# inktime_schematic.net
KiCad netlist of a schematic drawn in EAGLE
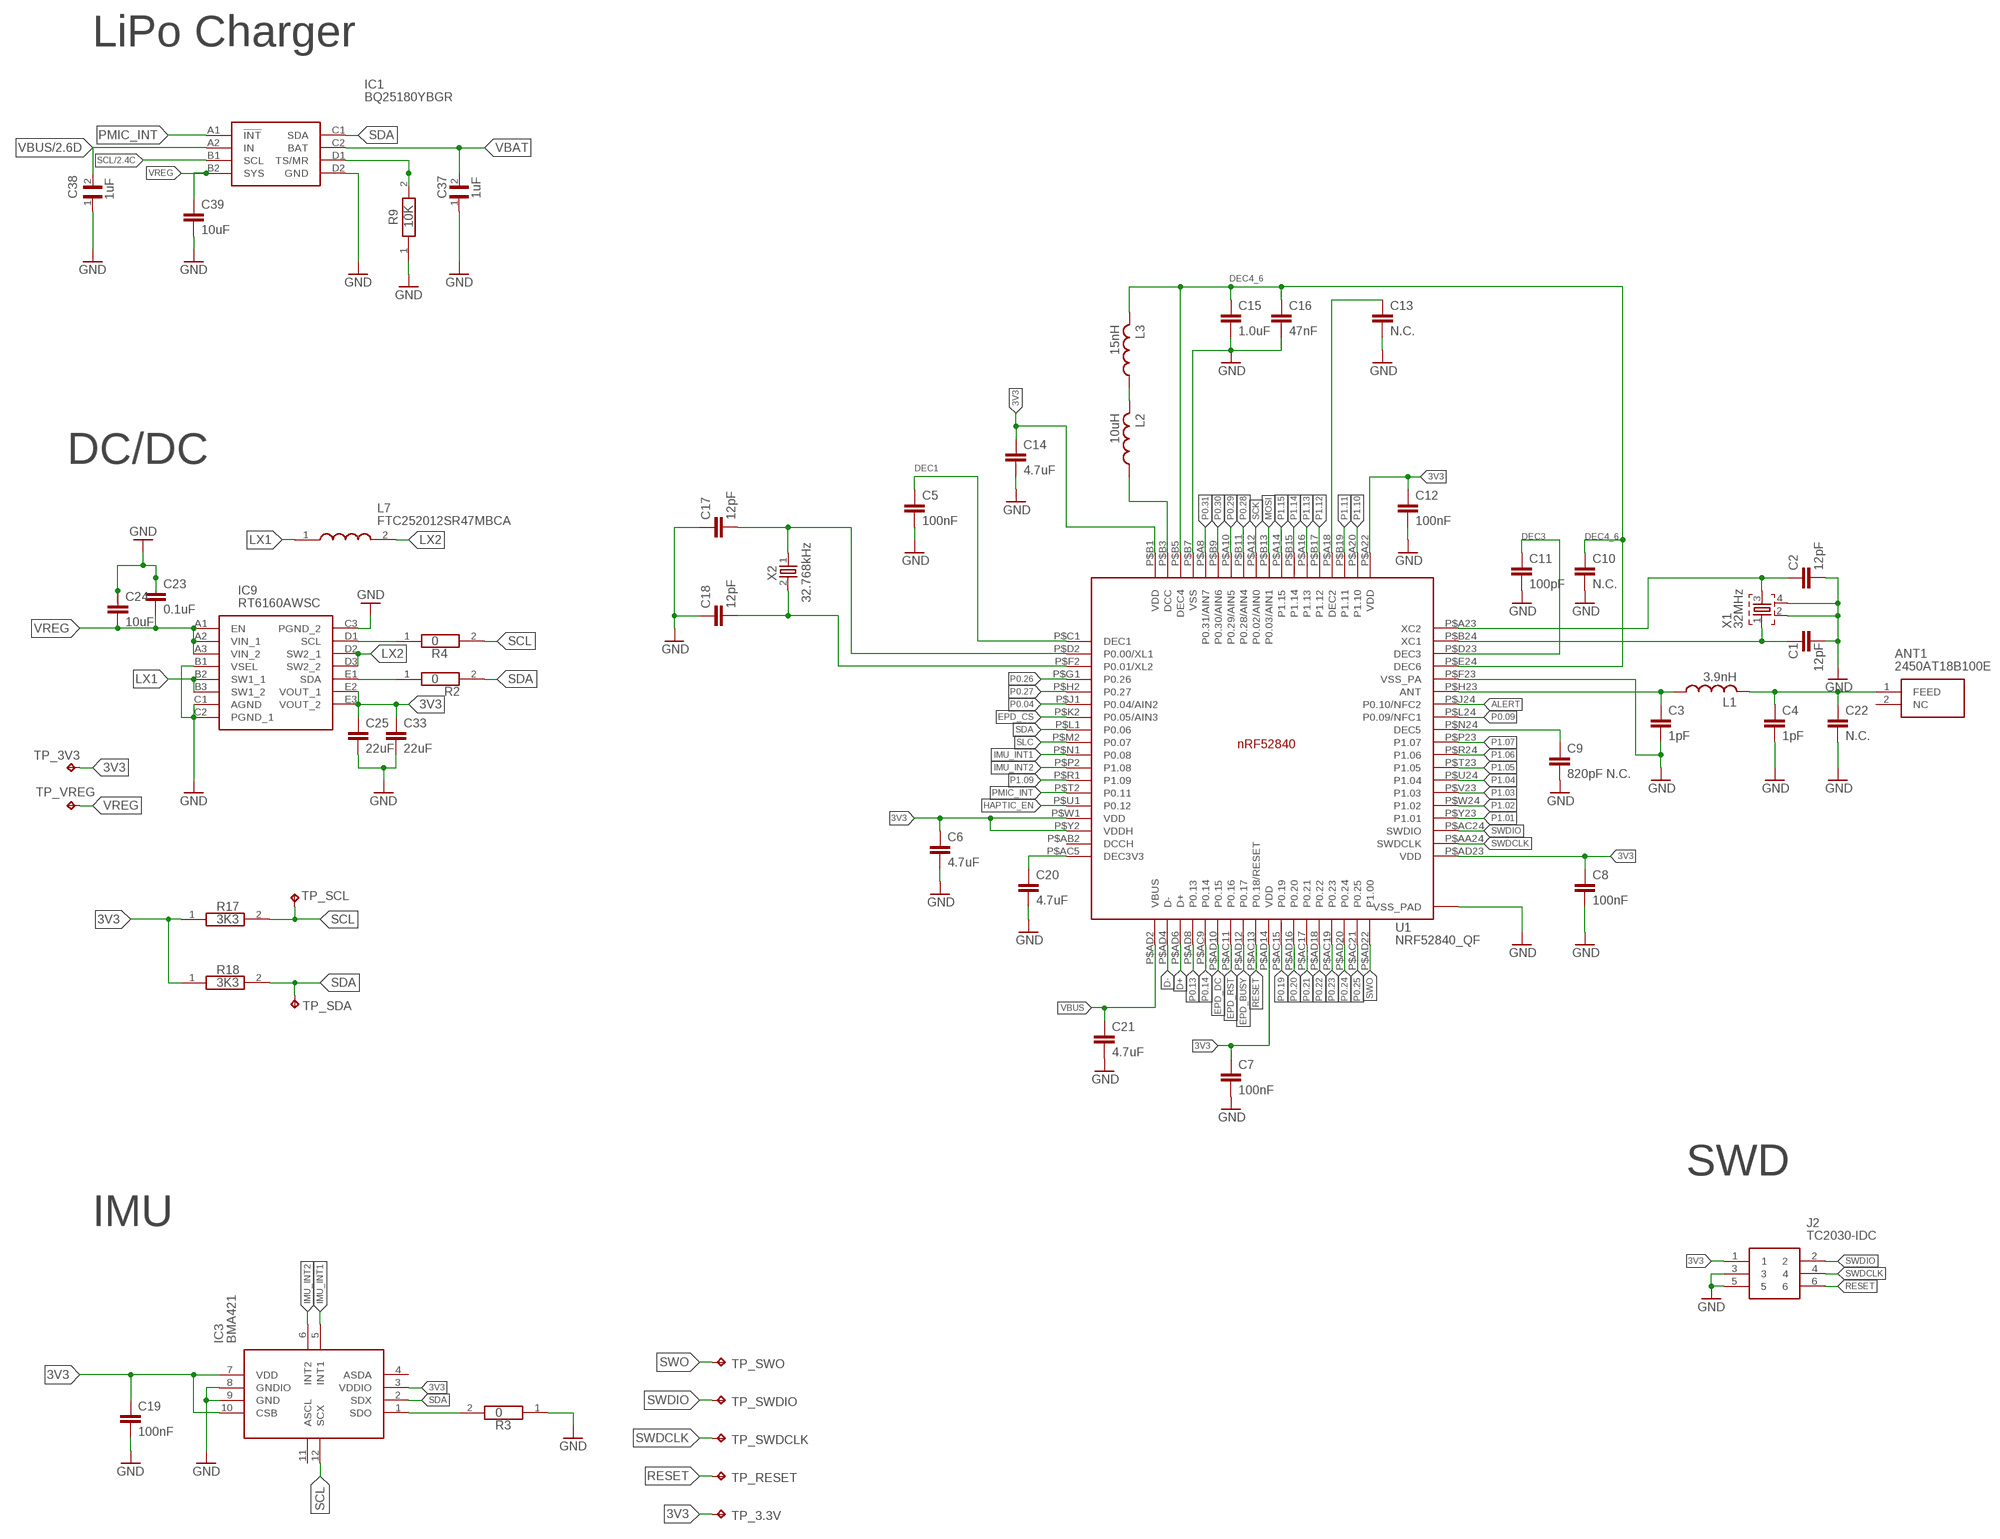
[diagram p0: schematic, sheet 1, part 1 of 2]
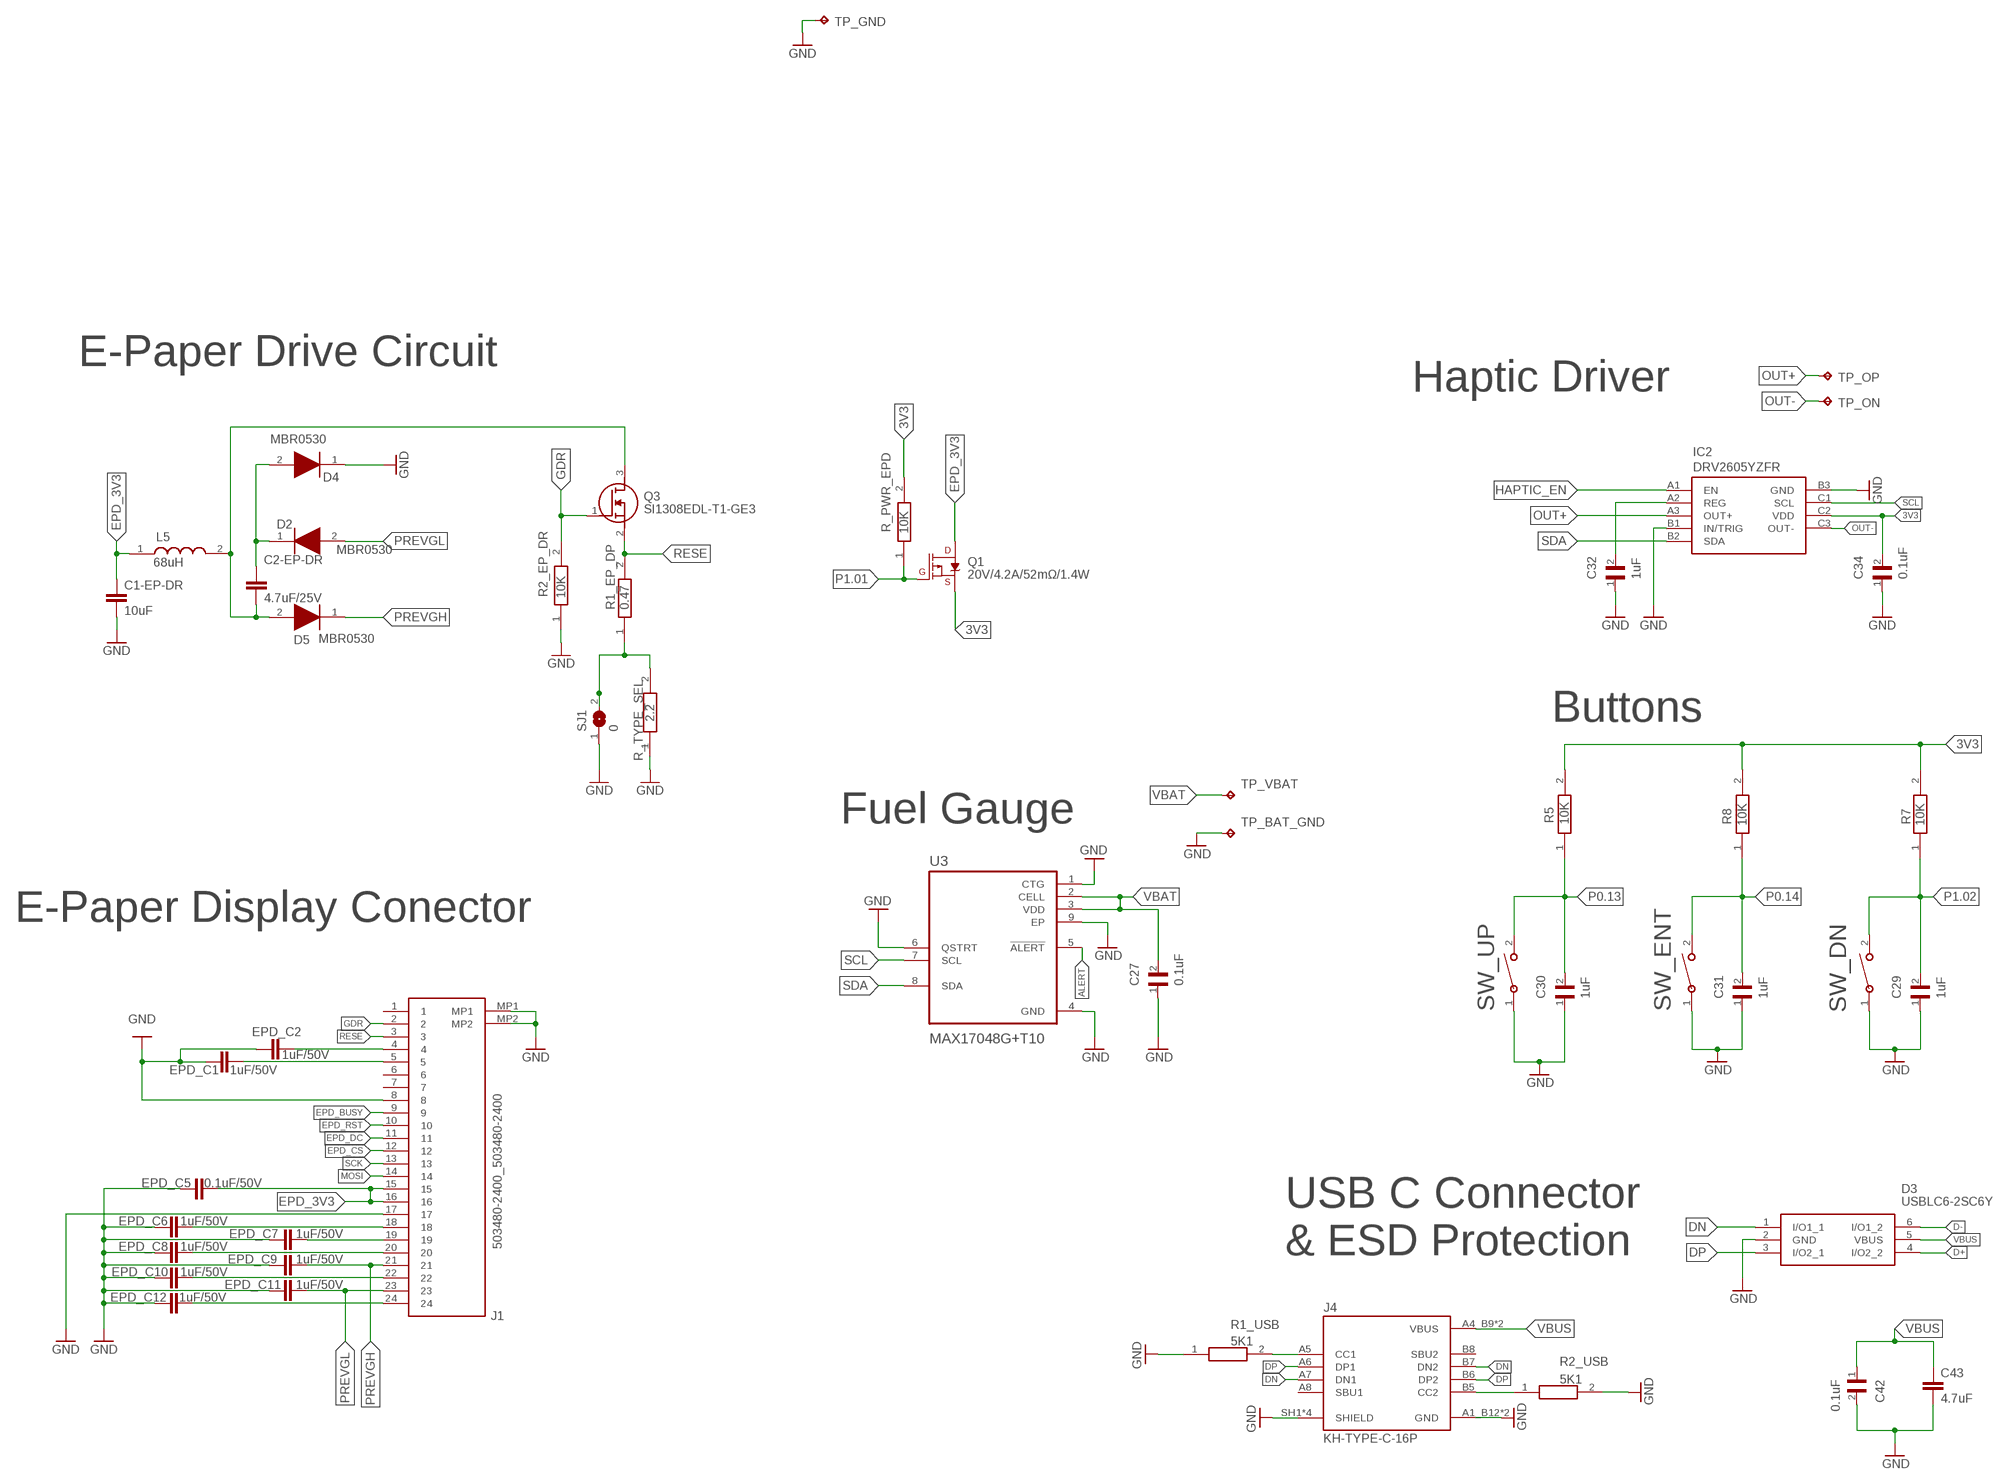
[diagram p1: schematic, sheet 1, part 2 of 2]

(export (version "E")
  (design (tool "Eeschema 10.0.6"))
  (components
    (comp (ref "ANT1")
      (value "2450AT18B100E")
      (footprint "eagle-import:2450AT18B100E_ANTC3216X140N")
      (fields (field (name "MOUSER_PART_NUMBER") "609-2450AT18B100E"))
      (libsource (lib "eagle-import") (part "2450AT18B100E_2450AT18B100E"))
    )
    (comp (ref "C1")
      (value "12pF")
      (footprint "eagle-import:NORDIC_NRF_3_RESC0201_L")
      (libsource (lib "eagle-import") (part "NORDIC_NRF_3_CAPACITOR_0201_L"))
    )
    (comp (ref "C1-EP-DR")
      (value "10uF")
      (footprint "eagle-import:NORDIC_NRF_3_RESC0201_L")
      (libsource (lib "eagle-import") (part "NORDIC_NRF_3_CAPACITOR_0201_L"))
    )
    (comp (ref "C2")
      (value "12pF")
      (footprint "eagle-import:NORDIC_NRF_3_RESC0201_L")
      (libsource (lib "eagle-import") (part "NORDIC_NRF_3_CAPACITOR_0201_L"))
    )
    (comp (ref "C2-EP-DR")
      (value "4.7uF/25V")
      (footprint "eagle-import:NORDIC_NRF_3_RESC0201_L")
      (libsource (lib "eagle-import") (part "NORDIC_NRF_3_CAPACITOR_0201_L"))
    )
    (comp (ref "C3")
      (value "1pF")
      (footprint "eagle-import:NORDIC_NRF_3_RESC0201_L")
      (libsource (lib "eagle-import") (part "NORDIC_NRF_3_CAPACITOR_0201_L"))
    )
    (comp (ref "C4")
      (value "1pF")
      (footprint "eagle-import:NORDIC_NRF_3_RESC0201_L")
      (libsource (lib "eagle-import") (part "NORDIC_NRF_3_CAPACITOR_0201_L"))
    )
    (comp (ref "C5")
      (value "100nF")
      (footprint "eagle-import:NORDIC_NRF_3_RESC0201_L")
      (libsource (lib "eagle-import") (part "NORDIC_NRF_3_CAPACITOR_0201_L"))
    )
    (comp (ref "C6")
      (value "4.7uF")
      (footprint "eagle-import:NORDIC_NRF_3_RESC0201_L")
      (libsource (lib "eagle-import") (part "NORDIC_NRF_3_CAPACITOR_0201_L"))
    )
    (comp (ref "C7")
      (value "100nF")
      (footprint "eagle-import:NORDIC_NRF_3_RESC0201_L")
      (libsource (lib "eagle-import") (part "NORDIC_NRF_3_CAPACITOR_0201_L"))
    )
    (comp (ref "C8")
      (value "100nF")
      (footprint "eagle-import:NORDIC_NRF_3_RESC0201_L")
      (libsource (lib "eagle-import") (part "NORDIC_NRF_3_CAPACITOR_0201_L"))
    )
    (comp (ref "C9")
      (value "820pF N.C.")
      (footprint "eagle-import:NORDIC_NRF_3_RESC0201_L")
      (libsource (lib "eagle-import") (part "NORDIC_NRF_3_CAPACITOR_0201_L"))
    )
    (comp (ref "C10")
      (value "N.C.")
      (footprint "eagle-import:NORDIC_NRF_3_RESC0201_L")
      (libsource (lib "eagle-import") (part "NORDIC_NRF_3_CAPACITOR_0201_L"))
    )
    (comp (ref "C11")
      (value "100pF")
      (footprint "eagle-import:NORDIC_NRF_3_RESC0201_L")
      (libsource (lib "eagle-import") (part "NORDIC_NRF_3_CAPACITOR_0201_L"))
    )
    (comp (ref "C12")
      (value "100nF")
      (footprint "eagle-import:NORDIC_NRF_3_RESC0201_L")
      (libsource (lib "eagle-import") (part "NORDIC_NRF_3_CAPACITOR_0201_L"))
    )
    (comp (ref "C13")
      (value "N.C.")
      (footprint "eagle-import:NORDIC_NRF_3_RESC0201_L")
      (libsource (lib "eagle-import") (part "NORDIC_NRF_3_CAPACITOR_0201_L"))
    )
    (comp (ref "C14")
      (value "4.7uF")
      (footprint "eagle-import:NORDIC_NRF_3_RESC0201_L")
      (libsource (lib "eagle-import") (part "NORDIC_NRF_3_CAPACITOR_0201_L"))
    )
    (comp (ref "C15")
      (value "1.0uF")
      (footprint "eagle-import:NORDIC_NRF_3_RESC0201_L")
      (libsource (lib "eagle-import") (part "NORDIC_NRF_3_CAPACITOR_0201_L"))
    )
    (comp (ref "C16")
      (value "47nF")
      (footprint "eagle-import:NORDIC_NRF_3_RESC0201_L")
      (libsource (lib "eagle-import") (part "NORDIC_NRF_3_CAPACITOR_0201_L"))
    )
    (comp (ref "C17")
      (value "12pF")
      (footprint "eagle-import:NORDIC_NRF_3_RESC0201_L")
      (libsource (lib "eagle-import") (part "NORDIC_NRF_3_CAPACITOR_0201_L"))
    )
    (comp (ref "C18")
      (value "12pF")
      (footprint "eagle-import:NORDIC_NRF_3_RESC0201_L")
      (libsource (lib "eagle-import") (part "NORDIC_NRF_3_CAPACITOR_0201_L"))
    )
    (comp (ref "C19")
      (value "100nF")
      (footprint "eagle-import:NORDIC_NRF_3_RESC0201_L")
      (libsource (lib "eagle-import") (part "NORDIC_NRF_3_CAPACITOR_0201_L"))
    )
    (comp (ref "C20")
      (value "4.7uF")
      (footprint "eagle-import:NORDIC_NRF_3_RESC0201_L")
      (libsource (lib "eagle-import") (part "NORDIC_NRF_3_CAPACITOR_0201_L"))
    )
    (comp (ref "C21")
      (value "4.7uF")
      (footprint "eagle-import:NORDIC_NRF_3_RESC0201_L")
      (libsource (lib "eagle-import") (part "NORDIC_NRF_3_CAPACITOR_0201_L"))
    )
    (comp (ref "C22")
      (value "N.C.")
      (footprint "eagle-import:NORDIC_NRF_3_RESC0201_L")
      (libsource (lib "eagle-import") (part "NORDIC_NRF_3_CAPACITOR_0201_L"))
    )
    (comp (ref "C23")
      (value "0.1uF")
      (footprint "eagle-import:NORDIC_NRF_3_RESC0201_L")
      (libsource (lib "eagle-import") (part "NORDIC_NRF_3_CAPACITOR_0201_L"))
    )
    (comp (ref "C24")
      (value "10uF")
      (footprint "eagle-import:NORDIC_NRF_3_RESC0201_L")
      (libsource (lib "eagle-import") (part "NORDIC_NRF_3_CAPACITOR_0201_L"))
    )
    (comp (ref "C25")
      (value "22uF")
      (footprint "eagle-import:NORDIC_NRF_3_RESC0201_L")
      (libsource (lib "eagle-import") (part "NORDIC_NRF_3_CAPACITOR_0201_L"))
    )
    (comp (ref "C27")
      (value "0.1uF")
      (footprint "eagle-import:GRM011R60J152KE01L_2_CAPC0201X13N")
      (fields (field (name "MF") "Murata") (field (name "MP") "GRM011R60J152KE01L"))
      (libsource (lib "eagle-import") (part "GRM011R60J152KE01L_2_GRM011R60J152KE01L"))
    )
    (comp (ref "C29")
      (value "1uF")
      (footprint "eagle-import:GRM011R60J152KE01L_2_CAPC0201X13N")
      (fields (field (name "MF") "Murata") (field (name "MP") "GRM011R60J152KE01L"))
      (libsource (lib "eagle-import") (part "GRM011R60J152KE01L_2_GRM011R60J152KE01L"))
    )
    (comp (ref "C30")
      (value "1uF")
      (footprint "eagle-import:GRM011R60J152KE01L_2_CAPC0201X13N")
      (fields (field (name "MF") "Murata") (field (name "MP") "GRM011R60J152KE01L"))
      (libsource (lib "eagle-import") (part "GRM011R60J152KE01L_2_GRM011R60J152KE01L"))
    )
    (comp (ref "C31")
      (value "1uF")
      (footprint "eagle-import:GRM011R60J152KE01L_2_CAPC0201X13N")
      (fields (field (name "MF") "Murata") (field (name "MP") "GRM011R60J152KE01L"))
      (libsource (lib "eagle-import") (part "GRM011R60J152KE01L_2_GRM011R60J152KE01L"))
    )
    (comp (ref "C32")
      (value "1uF")
      (footprint "eagle-import:GRM011R60J152KE01L_2_CAPC0201X13N")
      (fields (field (name "MF") "Murata") (field (name "MP") "GRM011R60J152KE01L"))
      (libsource (lib "eagle-import") (part "GRM011R60J152KE01L_2_GRM011R60J152KE01L"))
    )
    (comp (ref "C33")
      (value "22uF")
      (footprint "eagle-import:NORDIC_NRF_3_RESC0201_L")
      (libsource (lib "eagle-import") (part "NORDIC_NRF_3_CAPACITOR_0201_L"))
    )
    (comp (ref "C34")
      (value "0.1uF")
      (footprint "eagle-import:GRM011R60J152KE01L_2_CAPC0201X13N")
      (fields (field (name "MF") "Murata") (field (name "MP") "GRM011R60J152KE01L"))
      (libsource (lib "eagle-import") (part "GRM011R60J152KE01L_2_GRM011R60J152KE01L"))
    )
    (comp (ref "C37")
      (value "1uF")
      (footprint "eagle-import:GRM011R60J152KE01L_2_CAPC0201X13N")
      (fields (field (name "MF") "Murata") (field (name "MP") "GRM011R60J152KE01L"))
      (libsource (lib "eagle-import") (part "GRM011R60J152KE01L_2_GRM011R60J152KE01L"))
    )
    (comp (ref "C38")
      (value "1uF")
      (footprint "eagle-import:GRM011R60J152KE01L_2_CAPC0201X13N")
      (fields (field (name "MF") "Murata") (field (name "MP") "GRM011R60J152KE01L"))
      (libsource (lib "eagle-import") (part "GRM011R60J152KE01L_2_GRM011R60J152KE01L"))
    )
    (comp (ref "C39")
      (value "10uF")
      (footprint "eagle-import:NORDIC_NRF_3_RESC0201_L")
      (libsource (lib "eagle-import") (part "NORDIC_NRF_3_CAPACITOR_0201_L"))
    )
    (comp (ref "C42")
      (value "0.1uF")
      (footprint "eagle-import:GRM011R60J152KE01L_2_CAPC0201X13N")
      (fields (field (name "MF") "Murata") (field (name "MP") "GRM011R60J152KE01L"))
      (libsource (lib "eagle-import") (part "GRM011R60J152KE01L_2_GRM011R60J152KE01L"))
    )
    (comp (ref "C43")
      (value "4.7uF")
      (footprint "eagle-import:NORDIC_NRF_3_RESC0201_L")
      (libsource (lib "eagle-import") (part "NORDIC_NRF_3_CAPACITOR_0201_L"))
    )
    (comp (ref "D2")
      (value "MBR0530")
      (footprint "eagle-import:ESP32_C6_LIBRARY_5_SOD3716X135N")
      (fields (field (name "MF") "ON Semiconductor"))
      (libsource (lib "eagle-import") (part "ESP32_C6_LIBRARY_5_MBR0530"))
    )
    (comp (ref "D3")
      (value "USBLC6-2SC6Y")
      (footprint "eagle-import:ESP32_C6_LIBRARY_3_SOT95P280X145-6N")
      (fields (field (name "MF") "STMicroelectronics"))
      (libsource (lib "eagle-import") (part "ESP32_C6_LIBRARY_3_USBLC6-2SC6Y"))
    )
    (comp (ref "D4")
      (value "MBR0530")
      (footprint "eagle-import:ESP32_C6_LIBRARY_5_SOD3716X135N")
      (fields (field (name "MF") "ON Semiconductor"))
      (libsource (lib "eagle-import") (part "ESP32_C6_LIBRARY_5_MBR0530"))
    )
    (comp (ref "D5")
      (value "MBR0530")
      (footprint "eagle-import:ESP32_C6_LIBRARY_5_SOD3716X135N")
      (fields (field (name "MF") "ON Semiconductor"))
      (libsource (lib "eagle-import") (part "ESP32_C6_LIBRARY_5_MBR0530"))
    )
    (comp (ref "EPD_C1")
      (value "1uF/50V")
      (footprint "eagle-import:NORDIC_NRF_3_RESC0201_L")
      (libsource (lib "eagle-import") (part "NORDIC_NRF_3_CAPACITOR_0201_L"))
    )
    (comp (ref "EPD_C2")
      (value "1uF/50V")
      (footprint "eagle-import:NORDIC_NRF_3_RESC0201_L")
      (libsource (lib "eagle-import") (part "NORDIC_NRF_3_CAPACITOR_0201_L"))
    )
    (comp (ref "EPD_C5")
      (value "0.1uF/50V")
      (footprint "eagle-import:NORDIC_NRF_3_RESC0201_L")
      (libsource (lib "eagle-import") (part "NORDIC_NRF_3_CAPACITOR_0201_L"))
    )
    (comp (ref "EPD_C6")
      (value "1uF/50V")
      (footprint "eagle-import:NORDIC_NRF_3_RESC0201_L")
      (libsource (lib "eagle-import") (part "NORDIC_NRF_3_CAPACITOR_0201_L"))
    )
    (comp (ref "EPD_C7")
      (value "1uF/50V")
      (footprint "eagle-import:NORDIC_NRF_3_RESC0201_L")
      (libsource (lib "eagle-import") (part "NORDIC_NRF_3_CAPACITOR_0201_L"))
    )
    (comp (ref "EPD_C8")
      (value "1uF/50V")
      (footprint "eagle-import:NORDIC_NRF_3_RESC0201_L")
      (libsource (lib "eagle-import") (part "NORDIC_NRF_3_CAPACITOR_0201_L"))
    )
    (comp (ref "EPD_C9")
      (value "1uF/50V")
      (footprint "eagle-import:NORDIC_NRF_3_RESC0201_L")
      (libsource (lib "eagle-import") (part "NORDIC_NRF_3_CAPACITOR_0201_L"))
    )
    (comp (ref "EPD_C10")
      (value "1uF/50V")
      (footprint "eagle-import:NORDIC_NRF_3_RESC0201_L")
      (libsource (lib "eagle-import") (part "NORDIC_NRF_3_CAPACITOR_0201_L"))
    )
    (comp (ref "EPD_C11")
      (value "1uF/50V")
      (footprint "eagle-import:NORDIC_NRF_3_RESC0201_L")
      (libsource (lib "eagle-import") (part "NORDIC_NRF_3_CAPACITOR_0201_L"))
    )
    (comp (ref "EPD_C12")
      (value "1uF/50V")
      (footprint "eagle-import:NORDIC_NRF_3_RESC0201_L")
      (libsource (lib "eagle-import") (part "NORDIC_NRF_3_CAPACITOR_0201_L"))
    )
    (comp (ref "IC1")
      (value "BQ25180YBGR")
      (footprint "eagle-import:BQ25180YBGR_BGA8C40P2X4_100X155X50")
      (fields (field (name "MOUSER_PART_NUMBER") "595-BQ25180YBGR"))
      (libsource (lib "eagle-import") (part "BQ25180YBGR_BQ25180YBGR"))
    )
    (comp (ref "IC2")
      (value "DRV2605YZFR")
      (footprint "eagle-import:DRV2605YZFR_BGA9C50P3X3_144X144X62")
      (libsource (lib "eagle-import") (part "DRV2605YZFR_DRV2605YZFR"))
    )
    (comp (ref "IC3")
      (value "BMA421")
      (footprint "eagle-import:BMA423_BMA423")
      (fields (field (name "ARROW_PART_NUMBER") "BMA423") (field (name "MOUSER_PART_NUMBER") "262-BMA423"))
      (libsource (lib "eagle-import") (part "BMA423_BMA423"))
    )
    (comp (ref "IC9")
      (value "RT6160AWSC")
      (footprint "eagle-import:RT6160AWSC_BGA15C40P3X5_140X230X60")
      (fields (field (name "MOUSER_PART_NUMBER") "835-RT6160AWSC"))
      (libsource (lib "eagle-import") (part "RT6160AWSC_RT6160AWSC"))
    )
    (comp (ref "J1")
      (value "503480-2400_503480-2400")
      (footprint "eagle-import:503480-2400_5034802400")
      (fields
        (field (name "MANUFACTURER_PART_NUMBER") "503480-2400")
        (field (name "MOUSER_PART_NUMBER") "538-503480-2400")
      )
      (libsource (lib "eagle-import") (part "503480-2400_503480-2400"))
    )
    (comp (ref "J2")
      (value "TC2030-IDC")
      (footprint "eagle-import:TC2030-IDC_TC2030IDC")
      (libsource (lib "eagle-import") (part "TC2030-IDC_TC2030-IDC"))
    )
    (comp (ref "J4")
      (value "KH-TYPE-C-16P")
      (footprint "eagle-import:KH-TYPE-C-16P_KINGHELM_KH-TYPE-C-16P")
      (fields (field (name "MF") "kinghelm"))
      (libsource (lib "eagle-import") (part "KH-TYPE-C-16P_KH-TYPE-C-16P"))
    )
    (comp (ref "L1")
      (value "3.9nH")
      (footprint "eagle-import:NORDIC_NRF_2_RESC0402_L")
      (libsource (lib "eagle-import") (part "NORDIC_NRF_2_INDUCTOR_0402_L"))
    )
    (comp (ref "L2")
      (value "10uH")
      (footprint "eagle-import:NORDIC_NRF_2_RESC0402_L")
      (libsource (lib "eagle-import") (part "NORDIC_NRF_2_INDUCTOR_0402_L"))
    )
    (comp (ref "L3")
      (value "15nH")
      (footprint "eagle-import:NORDIC_NRF_2_RESC0402_L")
      (libsource (lib "eagle-import") (part "NORDIC_NRF_2_INDUCTOR_0402_L"))
    )
    (comp (ref "L5")
      (value "68uH")
      (footprint "eagle-import:MLP2016SR47MT0S1_INDC2016X100N")
      (fields (field (name "MANUFACTURER_PART_NUMBER") "FTC252012SR47MBCA"))
      (libsource (lib "eagle-import") (part "MLP2016SR47MT0S1_FTC252012SR47MBCA"))
    )
    (comp (ref "L7")
      (value "FTC252012SR47MBCA")
      (footprint "eagle-import:MLP2016SR47MT0S1_INDC2016X100N")
      (libsource (lib "eagle-import") (part "MLP2016SR47MT0S1_FTC252012SR47MBCA"))
    )
    (comp (ref "Q1")
      (value "20V/4.2A/52mΩ/1.4W")
      (footprint "eagle-import:ESP32_C6_LIBRARY_4_ESP32_C6_LIBRARY_4_ESP32_C6_LIBRARY_4_ESP32_C6_LIBRARY_4_ESP32_WROVER_SPARKFUN-DISCRETESEMI_SOT23-3")
      (libsource (lib "eagle-import") (part "ESP32_C6_LIBRARY_4_ESP32_WROVER_SPARKFUN-DISCRETESEMI_MOSFET_PCH-DMG2305UX-7"))
    )
    (comp (ref "Q3")
      (value "SI1308EDL-T1-GE3")
      (footprint "eagle-import:ESP32_C6_LIBRARY_6_SOT65P210X110-3N")
      (fields (field (name "MF") "Vishay Siliconix"))
      (libsource (lib "eagle-import") (part "ESP32_C6_LIBRARY_6_SI1308EDL-T1-GE3"))
    )
    (comp (ref "R1_EP_DP")
      (value "0.47")
      (footprint "eagle-import:CPF0201D7K68C1_0201")
      (libsource (lib "eagle-import") (part "CPF0201D7K68C1_CPF0201D7K68C1"))
    )
    (comp (ref "R1_USB")
      (value "5K1")
      (footprint "eagle-import:CPF0201D7K68C1_0201")
      (libsource (lib "eagle-import") (part "CPF0201D7K68C1_CPF0201D7K68C1"))
    )
    (comp (ref "R2")
      (value "0")
      (footprint "eagle-import:CPF0201D7K68C1_0201")
      (libsource (lib "eagle-import") (part "CPF0201D7K68C1_CPF0201D7K68C1"))
    )
    (comp (ref "R2_EP_DR")
      (value "10K")
      (footprint "eagle-import:CPF0201D7K68C1_0201")
      (libsource (lib "eagle-import") (part "CPF0201D7K68C1_CPF0201D7K68C1"))
    )
    (comp (ref "R2_USB")
      (value "5K1")
      (footprint "eagle-import:CPF0201D7K68C1_0201")
      (libsource (lib "eagle-import") (part "CPF0201D7K68C1_CPF0201D7K68C1"))
    )
    (comp (ref "R3")
      (value "0")
      (footprint "eagle-import:CPF0201D7K68C1_0201")
      (libsource (lib "eagle-import") (part "CPF0201D7K68C1_CPF0201D7K68C1"))
    )
    (comp (ref "R4")
      (value "0")
      (footprint "eagle-import:CPF0201D7K68C1_0201")
      (libsource (lib "eagle-import") (part "CPF0201D7K68C1_CPF0201D7K68C1"))
    )
    (comp (ref "R5")
      (value "10K")
      (footprint "eagle-import:CPF0201D7K68C1_0201")
      (libsource (lib "eagle-import") (part "CPF0201D7K68C1_CPF0201D7K68C1"))
    )
    (comp (ref "R7")
      (value "10K")
      (footprint "eagle-import:CPF0201D7K68C1_0201")
      (libsource (lib "eagle-import") (part "CPF0201D7K68C1_CPF0201D7K68C1"))
    )
    (comp (ref "R8")
      (value "10K")
      (footprint "eagle-import:CPF0201D7K68C1_0201")
      (libsource (lib "eagle-import") (part "CPF0201D7K68C1_CPF0201D7K68C1"))
    )
    (comp (ref "R9")
      (value "10K")
      (footprint "eagle-import:CPF0201D7K68C1_0201")
      (libsource (lib "eagle-import") (part "CPF0201D7K68C1_CPF0201D7K68C1"))
    )
    (comp (ref "R17")
      (value "3K3")
      (footprint "eagle-import:CPF0201D7K68C1_0201")
      (libsource (lib "eagle-import") (part "CPF0201D7K68C1_CPF0201D7K68C1"))
    )
    (comp (ref "R18")
      (value "3K3")
      (footprint "eagle-import:CPF0201D7K68C1_0201")
      (libsource (lib "eagle-import") (part "CPF0201D7K68C1_CPF0201D7K68C1"))
    )
    (comp (ref "R_PWR_EPD")
      (value "10K")
      (footprint "eagle-import:CPF0201D7K68C1_0201")
      (libsource (lib "eagle-import") (part "CPF0201D7K68C1_CPF0201D7K68C1"))
    )
    (comp (ref "R_TYPE_SEL")
      (value "2.2")
      (footprint "eagle-import:CPF0201D7K68C1_0201")
      (libsource (lib "eagle-import") (part "CPF0201D7K68C1_CPF0201D7K68C1"))
    )
    (comp (ref "SJ1")
      (value "0")
      (footprint "eagle-import:ESP32_C6_LIBRARY_7_JUMPER_SJ")
      (libsource (lib "eagle-import") (part "ESP32_C6_LIBRARY_7_JUMPER_SJ"))
    )
    (comp (ref "SW_DN")
      (value "2025-10-22_07-23-44_LIBRARY_EVP-AKE31ASW_EVP-AKE31A_PAN")
      (footprint "eagle-import:2025-10-22_07-23-44_LIBRARY_SW_EVP-AKE31A_PAN")
      (fields
        (field (name "MANUFACTURER_PART_NUMBER") "EVP-AKE31A")
        (field (name "COPYRIGHT") "Copyright (C) 2025 Ultra Librarian. All rights reserved.")
      )
      (libsource (lib "eagle-import") (part "2025-10-22_07-23-44_LIBRARY_EVP-AKE31ASW_EVP-AKE31A_PAN"))
    )
    (comp (ref "SW_ENT")
      (value "2025-10-22_07-23-44_LIBRARY_EVP-AKE31ASW_EVP-AKE31A_PAN")
      (footprint "eagle-import:2025-10-22_07-23-44_LIBRARY_SW_EVP-AKE31A_PAN")
      (fields
        (field (name "MANUFACTURER_PART_NUMBER") "EVP-AKE31A")
        (field (name "COPYRIGHT") "Copyright (C) 2025 Ultra Librarian. All rights reserved.")
      )
      (libsource (lib "eagle-import") (part "2025-10-22_07-23-44_LIBRARY_EVP-AKE31ASW_EVP-AKE31A_PAN"))
    )
    (comp (ref "SW_UP")
      (value "2025-10-22_07-23-44_LIBRARY_EVP-AKE31ASW_EVP-AKE31A_PAN")
      (footprint "eagle-import:2025-10-22_07-23-44_LIBRARY_SW_EVP-AKE31A_PAN")
      (fields
        (field (name "MANUFACTURER_PART_NUMBER") "EVP-AKE31A")
        (field (name "COPYRIGHT") "Copyright (C) 2025 Ultra Librarian. All rights reserved.")
      )
      (libsource (lib "eagle-import") (part "2025-10-22_07-23-44_LIBRARY_EVP-AKE31ASW_EVP-AKE31A_PAN"))
    )
    (comp (ref "TP_3.3V")
      (value "HECTOR_WATCH_1_TPTP20R")
      (footprint "eagle-import:HECTOR_WATCH_1_TP20R")
      (libsource (lib "eagle-import") (part "HECTOR_WATCH_1_TPTP20R"))
    )
    (comp (ref "TP_3V3")
      (value "HECTOR_WATCH_1_TPTP20R")
      (footprint "eagle-import:HECTOR_WATCH_1_TP20R")
      (libsource (lib "eagle-import") (part "HECTOR_WATCH_1_TPTP20R"))
    )
    (comp (ref "TP_BAT_GND")
      (value "HECTOR_WATCH_1_TPTP20R")
      (footprint "eagle-import:HECTOR_WATCH_1_TP20R")
      (libsource (lib "eagle-import") (part "HECTOR_WATCH_1_TPTP20R"))
    )
    (comp (ref "TP_GND")
      (value "HECTOR_WATCH_1_TPTP20R")
      (footprint "eagle-import:HECTOR_WATCH_1_TP20R")
      (libsource (lib "eagle-import") (part "HECTOR_WATCH_1_TPTP20R"))
    )
    (comp (ref "TP_ON")
      (value "HECTOR_WATCH_1_TPTP20R")
      (footprint "eagle-import:HECTOR_WATCH_1_TP20R")
      (libsource (lib "eagle-import") (part "HECTOR_WATCH_1_TPTP20R"))
    )
    (comp (ref "TP_OP")
      (value "HECTOR_WATCH_1_TPTP20R")
      (footprint "eagle-import:HECTOR_WATCH_1_TP20R")
      (libsource (lib "eagle-import") (part "HECTOR_WATCH_1_TPTP20R"))
    )
    (comp (ref "TP_RESET")
      (value "HECTOR_WATCH_1_TPTP20R")
      (footprint "eagle-import:HECTOR_WATCH_1_TP20R")
      (libsource (lib "eagle-import") (part "HECTOR_WATCH_1_TPTP20R"))
    )
    (comp (ref "TP_SCL")
      (value "HECTOR_WATCH_1_TPTP20R")
      (footprint "eagle-import:HECTOR_WATCH_1_TP20R")
      (libsource (lib "eagle-import") (part "HECTOR_WATCH_1_TPTP20R"))
    )
    (comp (ref "TP_SDA")
      (value "HECTOR_WATCH_1_TPTP20R")
      (footprint "eagle-import:HECTOR_WATCH_1_TP20R")
      (libsource (lib "eagle-import") (part "HECTOR_WATCH_1_TPTP20R"))
    )
    (comp (ref "TP_SWDCLK")
      (value "HECTOR_WATCH_1_TPTP20R")
      (footprint "eagle-import:HECTOR_WATCH_1_TP20R")
      (libsource (lib "eagle-import") (part "HECTOR_WATCH_1_TPTP20R"))
    )
    (comp (ref "TP_SWDIO")
      (value "HECTOR_WATCH_1_TPTP20R")
      (footprint "eagle-import:HECTOR_WATCH_1_TP20R")
      (libsource (lib "eagle-import") (part "HECTOR_WATCH_1_TPTP20R"))
    )
    (comp (ref "TP_SWO")
      (value "HECTOR_WATCH_1_TPTP20R")
      (footprint "eagle-import:HECTOR_WATCH_1_TP20R")
      (libsource (lib "eagle-import") (part "HECTOR_WATCH_1_TPTP20R"))
    )
    (comp (ref "TP_VBAT")
      (value "HECTOR_WATCH_1_TPTP20R")
      (footprint "eagle-import:HECTOR_WATCH_1_TP20R")
      (libsource (lib "eagle-import") (part "HECTOR_WATCH_1_TPTP20R"))
    )
    (comp (ref "TP_VREG")
      (value "HECTOR_WATCH_1_TPTP20R")
      (footprint "eagle-import:HECTOR_WATCH_1_TP20R")
      (libsource (lib "eagle-import") (part "HECTOR_WATCH_1_TPTP20R"))
    )
    (comp (ref "U1")
      (value "NRF52840_QF")
      (footprint "eagle-import:NORDIC_NRF_4_AQFN50P700X700X85_HS-74N")
      (libsource (lib "eagle-import") (part "NORDIC_NRF_4_NRF52840_QF"))
    )
    (comp (ref "U3")
      (value "MAX17048G+T10")
      (footprint "eagle-import:ESP32_C6_LIBRARY_SON50P200X200X80-9N")
      (fields (field (name "MF") "Analog Devices"))
      (libsource (lib "eagle-import") (part "ESP32_C6_LIBRARY_MAX17048G+T10"))
    )
    (comp (ref "X1")
      (value "32MHz")
      (footprint "eagle-import:NORDIC_NRF_BT-XTAL_2016_N")
      (libsource (lib "eagle-import") (part "NORDIC_NRF_XTAL_32MHZ"))
    )
    (comp (ref "X2")
      (value "32.768kHz")
      (footprint "eagle-import:NORDIC_NRF_1_XTAL_3215_N")
      (libsource (lib "eagle-import") (part "NORDIC_NRF_1_XTAL_32KHZ"))
    )
  )
  (nets
    (net (code "1") (name "/DEC1") (class "Default")
      (node (ref "C5") (pin "1") (pinfunction "1_1") (pintype "passive"))
      (node (ref "U1") (pin "P$C1") (pinfunction "DEC1_P$C1") (pintype "power_in"))
    )
    (net (code "2") (name "/DEC3") (class "Default")
      (node (ref "C11") (pin "1") (pinfunction "1_1") (pintype "passive"))
      (node (ref "U1") (pin "P$D23") (pinfunction "DEC3_P$D23") (pintype "bidirectional"))
    )
    (net (code "3") (name "/DEC4_6") (class "Default")
      (node (ref "C10") (pin "1") (pinfunction "1_1") (pintype "passive"))
      (node (ref "C15") (pin "1") (pinfunction "1_1") (pintype "passive"))
      (node (ref "C16") (pin "1") (pinfunction "1_1") (pintype "passive"))
      (node (ref "L3") (pin "2") (pinfunction "2_2") (pintype "passive"))
      (node (ref "U1") (pin "P$B5") (pinfunction "DEC4_P$B5") (pintype "power_in"))
      (node (ref "U1") (pin "P$E24") (pinfunction "DEC6_P$E24") (pintype "bidirectional"))
    )
    (net (code "4") (name "3V3") (class "Default")
      (node (ref "C12") (pin "1") (pinfunction "1_1") (pintype "passive"))
      (node (ref "C14") (pin "1") (pinfunction "1_1") (pintype "passive"))
      (node (ref "C19") (pin "1") (pinfunction "1_1") (pintype "passive"))
      (node (ref "C25") (pin "1") (pinfunction "1_1") (pintype "passive"))
      (node (ref "C33") (pin "1") (pinfunction "1_1") (pintype "passive"))
      (node (ref "C34") (pin "2") (pinfunction "2_2") (pintype "passive"))
      (node (ref "C6") (pin "1") (pinfunction "1_1") (pintype "passive"))
      (node (ref "C7") (pin "1") (pinfunction "1_1") (pintype "passive"))
      (node (ref "C8") (pin "1") (pinfunction "1_1") (pintype "passive"))
      (node (ref "IC2") (pin "C2") (pinfunction "VDD_C2") (pintype "bidirectional"))
      (node (ref "IC3") (pin "10") (pinfunction "CSB_10") (pintype "bidirectional"))
      (node (ref "IC3") (pin "3") (pinfunction "VDDIO_3") (pintype "bidirectional"))
      (node (ref "IC3") (pin "7") (pinfunction "VDD_7") (pintype "bidirectional"))
      (node (ref "IC9") (pin "E2") (pinfunction "VOUT_1_E2") (pintype "bidirectional"))
      (node (ref "IC9") (pin "E3") (pinfunction "VOUT_2_E3") (pintype "bidirectional"))
      (node (ref "J2") (pin "1") (pinfunction "1_1") (pintype "bidirectional"))
      (node (ref "Q1") (pin "2") (pinfunction "S_2") (pintype "bidirectional"))
      (node (ref "R17") (pin "1") (pinfunction "1_1") (pintype "bidirectional"))
      (node (ref "R18") (pin "1") (pinfunction "1_1") (pintype "bidirectional"))
      (node (ref "R5") (pin "2") (pinfunction "2_2") (pintype "bidirectional"))
      (node (ref "R7") (pin "2") (pinfunction "2_2") (pintype "bidirectional"))
      (node (ref "R8") (pin "2") (pinfunction "2_2") (pintype "bidirectional"))
      (node (ref "R_PWR_EPD") (pin "2") (pinfunction "2_2") (pintype "bidirectional"))
      (node (ref "TP_3.3V") (pin "TP") (pinfunction "TP_TP") (pintype "input"))
      (node (ref "TP_3V3") (pin "TP") (pinfunction "TP_TP") (pintype "input"))
      (node (ref "U1") (pin "P$A22") (pinfunction "VDD_P$A22") (pintype "power_in"))
      (node (ref "U1") (pin "P$AD14") (pinfunction "VDD_P$AD14") (pintype "power_in"))
      (node (ref "U1") (pin "P$AD23") (pinfunction "VDD_P$AD23") (pintype "power_in"))
      (node (ref "U1") (pin "P$B1") (pinfunction "VDD_P$B1") (pintype "power_in"))
      (node (ref "U1") (pin "P$W1") (pinfunction "VDD_P$W1") (pintype "power_in"))
      (node (ref "U1") (pin "P$Y2") (pinfunction "VDDH_P$Y2") (pintype "power_in"))
    )
    (net (code "5") (name "ALERT") (class "Default")
      (node (ref "U1") (pin "P$J24") (pinfunction "P0.10/NFC2_P$J24") (pintype "bidirectional"))
      (node (ref "U3") (pin "5") (pinfunction "~{ALERT}_5") (pintype "output"))
    )
    (net (code "6") (name "D+") (class "Default")
      (node (ref "D3") (pin "4") (pinfunction "I/O2_2_4") (pintype "bidirectional"))
      (node (ref "U1") (pin "P$AD6") (pinfunction "D+_P$AD6") (pintype "bidirectional"))
    )
    (net (code "7") (name "D-") (class "Default")
      (node (ref "D3") (pin "6") (pinfunction "I/O1_2_6") (pintype "bidirectional"))
      (node (ref "U1") (pin "P$AD4") (pinfunction "D-_P$AD4") (pintype "bidirectional"))
    )
    (net (code "8") (name "DN") (class "Default")
      (node (ref "D3") (pin "1") (pinfunction "I/O1_1_1") (pintype "bidirectional"))
      (node (ref "J4") (pin "A7") (pinfunction "DN1_A7") (pintype "bidirectional"))
      (node (ref "J4") (pin "B7") (pinfunction "DN2_B7") (pintype "bidirectional"))
    )
    (net (code "9") (name "DP") (class "Default")
      (node (ref "D3") (pin "3") (pinfunction "I/O2_1_3") (pintype "bidirectional"))
      (node (ref "J4") (pin "A6") (pinfunction "DP1_A6") (pintype "bidirectional"))
      (node (ref "J4") (pin "B6") (pinfunction "DP2_B6") (pintype "bidirectional"))
    )
    (net (code "10") (name "EPD_3V3") (class "Default")
      (node (ref "C1-EP-DR") (pin "1") (pinfunction "1_1") (pintype "passive"))
      (node (ref "EPD_C5") (pin "2") (pinfunction "2_2") (pintype "passive"))
      (node (ref "J1") (pin "15") (pinfunction "15_15") (pintype "bidirectional"))
      (node (ref "J1") (pin "16") (pinfunction "16_16") (pintype "bidirectional"))
      (node (ref "L5") (pin "1") (pinfunction "1_1") (pintype "bidirectional"))
      (node (ref "Q1") (pin "3") (pinfunction "D_3") (pintype "bidirectional"))
    )
    (net (code "11") (name "EPD_BUSY") (class "Default")
      (node (ref "J1") (pin "9") (pinfunction "9_9") (pintype "bidirectional"))
      (node (ref "U1") (pin "P$AD12") (pinfunction "P0.17_P$AD12") (pintype "bidirectional"))
    )
    (net (code "12") (name "EPD_CS") (class "Default")
      (node (ref "J1") (pin "12") (pinfunction "12_12") (pintype "bidirectional"))
      (node (ref "U1") (pin "P$K2") (pinfunction "P0.05/AIN3_P$K2") (pintype "bidirectional"))
    )
    (net (code "13") (name "EPD_DC") (class "Default")
      (node (ref "J1") (pin "11") (pinfunction "11_11") (pintype "bidirectional"))
      (node (ref "U1") (pin "P$AD10") (pinfunction "P0.15_P$AD10") (pintype "bidirectional"))
    )
    (net (code "14") (name "EPD_RST") (class "Default")
      (node (ref "J1") (pin "10") (pinfunction "10_10") (pintype "bidirectional"))
      (node (ref "U1") (pin "P$AC11") (pinfunction "P0.16_P$AC11") (pintype "bidirectional"))
    )
    (net (code "15") (name "GDR") (class "Default")
      (node (ref "J1") (pin "2") (pinfunction "2_2") (pintype "bidirectional"))
      (node (ref "Q3") (pin "1") (pinfunction "G_1") (pintype "bidirectional"))
      (node (ref "R2_EP_DR") (pin "2") (pinfunction "2_2") (pintype "bidirectional"))
    )
    (net (code "16") (name "GND") (class "Default")
      (node (ref "C1") (pin "2") (pinfunction "2_2") (pintype "passive"))
      (node (ref "C1-EP-DR") (pin "2") (pinfunction "2_2") (pintype "passive"))
      (node (ref "C10") (pin "2") (pinfunction "2_2") (pintype "passive"))
      (node (ref "C11") (pin "2") (pinfunction "2_2") (pintype "passive"))
      (node (ref "C12") (pin "2") (pinfunction "2_2") (pintype "passive"))
      (node (ref "C13") (pin "2") (pinfunction "2_2") (pintype "passive"))
      (node (ref "C14") (pin "2") (pinfunction "2_2") (pintype "passive"))
      (node (ref "C15") (pin "2") (pinfunction "2_2") (pintype "passive"))
      (node (ref "C16") (pin "2") (pinfunction "2_2") (pintype "passive"))
      (node (ref "C17") (pin "1") (pinfunction "1_1") (pintype "passive"))
      (node (ref "C18") (pin "1") (pinfunction "1_1") (pintype "passive"))
      (node (ref "C19") (pin "2") (pinfunction "2_2") (pintype "passive"))
      (node (ref "C2") (pin "2") (pinfunction "2_2") (pintype "passive"))
      (node (ref "C20") (pin "2") (pinfunction "2_2") (pintype "passive"))
      (node (ref "C21") (pin "2") (pinfunction "2_2") (pintype "passive"))
      (node (ref "C22") (pin "2") (pinfunction "2_2") (pintype "passive"))
      (node (ref "C23") (pin "1") (pinfunction "1_1") (pintype "passive"))
      (node (ref "C24") (pin "1") (pinfunction "1_1") (pintype "passive"))
      (node (ref "C25") (pin "2") (pinfunction "2_2") (pintype "passive"))
      (node (ref "C27") (pin "1") (pinfunction "1_1") (pintype "passive"))
      (node (ref "C29") (pin "1") (pinfunction "1_1") (pintype "passive"))
      (node (ref "C3") (pin "2") (pinfunction "2_2") (pintype "passive"))
      (node (ref "C30") (pin "1") (pinfunction "1_1") (pintype "passive"))
      (node (ref "C31") (pin "1") (pinfunction "1_1") (pintype "passive"))
      (node (ref "C32") (pin "1") (pinfunction "1_1") (pintype "passive"))
      (node (ref "C33") (pin "2") (pinfunction "2_2") (pintype "passive"))
      (node (ref "C34") (pin "1") (pinfunction "1_1") (pintype "passive"))
      (node (ref "C37") (pin "1") (pinfunction "1_1") (pintype "passive"))
      (node (ref "C38") (pin "1") (pinfunction "1_1") (pintype "passive"))
      (node (ref "C39") (pin "2") (pinfunction "2_2") (pintype "passive"))
      (node (ref "C4") (pin "2") (pinfunction "2_2") (pintype "passive"))
      (node (ref "C42") (pin "2") (pinfunction "2_2") (pintype "passive"))
      (node (ref "C43") (pin "2") (pinfunction "2_2") (pintype "passive"))
      (node (ref "C5") (pin "2") (pinfunction "2_2") (pintype "passive"))
      (node (ref "C6") (pin "2") (pinfunction "2_2") (pintype "passive"))
      (node (ref "C7") (pin "2") (pinfunction "2_2") (pintype "passive"))
      (node (ref "C8") (pin "2") (pinfunction "2_2") (pintype "passive"))
      (node (ref "C9") (pin "2") (pinfunction "2_2") (pintype "passive"))
      (node (ref "D3") (pin "2") (pinfunction "GND_2") (pintype "bidirectional"))
      (node (ref "D4") (pin "1") (pinfunction "K_1") (pintype "bidirectional"))
      (node (ref "EPD_C1") (pin "1") (pinfunction "1_1") (pintype "passive"))
      (node (ref "EPD_C10") (pin "1") (pinfunction "1_1") (pintype "passive"))
      (node (ref "EPD_C11") (pin "1") (pinfunction "1_1") (pintype "passive"))
      (node (ref "EPD_C12") (pin "1") (pinfunction "1_1") (pintype "passive"))
      (node (ref "EPD_C2") (pin "1") (pinfunction "1_1") (pintype "passive"))
      (node (ref "EPD_C5") (pin "1") (pinfunction "1_1") (pintype "passive"))
      (node (ref "EPD_C6") (pin "1") (pinfunction "1_1") (pintype "passive"))
      (node (ref "EPD_C7") (pin "1") (pinfunction "1_1") (pintype "passive"))
      (node (ref "EPD_C8") (pin "1") (pinfunction "1_1") (pintype "passive"))
      (node (ref "EPD_C9") (pin "1") (pinfunction "1_1") (pintype "passive"))
      (node (ref "IC1") (pin "D2") (pinfunction "GND_D2") (pintype "bidirectional"))
      (node (ref "IC2") (pin "B1") (pinfunction "IN/TRIG_B1") (pintype "bidirectional"))
      (node (ref "IC2") (pin "B3") (pinfunction "GND_B3") (pintype "bidirectional"))
      (node (ref "IC3") (pin "8") (pinfunction "GNDIO_8") (pintype "bidirectional"))
      (node (ref "IC3") (pin "9") (pinfunction "GND_9") (pintype "bidirectional"))
      (node (ref "IC9") (pin "B1") (pinfunction "VSEL_B1") (pintype "bidirectional"))
      (node (ref "IC9") (pin "C1") (pinfunction "AGND_C1") (pintype "bidirectional"))
      (node (ref "IC9") (pin "C2") (pinfunction "PGND_1_C2") (pintype "bidirectional"))
      (node (ref "IC9") (pin "C3") (pinfunction "PGND_2_C3") (pintype "bidirectional"))
      (node (ref "J1") (pin "17") (pinfunction "17_17") (pintype "bidirectional"))
      (node (ref "J1") (pin "8") (pinfunction "8_8") (pintype "bidirectional"))
      (node (ref "J1") (pin "MP1") (pinfunction "MP1_MP1") (pintype "bidirectional"))
      (node (ref "J1") (pin "MP2") (pinfunction "MP2_MP2") (pintype "bidirectional"))
      (node (ref "J2") (pin "3") (pinfunction "3_3") (pintype "bidirectional"))
      (node (ref "J2") (pin "5") (pinfunction "5_5") (pintype "bidirectional"))
      (node (ref "J4") (pin "A12_B1") (pinfunction "GND_A12_B1") (pintype "power_in"))
      (node (ref "J4") (pin "A1_B12") (pinfunction "GND_A1_B12") (pintype "power_in"))
      (node (ref "J4") (pin "SH1") (pinfunction "SHIELD_SH1") (pintype "passive"))
      (node (ref "J4") (pin "SH2") (pinfunction "SHIELD_SH2") (pintype "passive"))
      (node (ref "J4") (pin "SH3") (pinfunction "SHIELD_SH3") (pintype "passive"))
      (node (ref "J4") (pin "SH4") (pinfunction "SHIELD_SH4") (pintype "passive"))
      (node (ref "R1_USB") (pin "1") (pinfunction "1_1") (pintype "bidirectional"))
      (node (ref "R2_EP_DR") (pin "1") (pinfunction "1_1") (pintype "bidirectional"))
      (node (ref "R2_USB") (pin "2") (pinfunction "2_2") (pintype "bidirectional"))
      (node (ref "R3") (pin "1") (pinfunction "1_1") (pintype "bidirectional"))
      (node (ref "R9") (pin "1") (pinfunction "1_1") (pintype "bidirectional"))
      (node (ref "R_TYPE_SEL") (pin "1") (pinfunction "1_1") (pintype "bidirectional"))
      (node (ref "SJ1") (pin "1") (pinfunction "1_1") (pintype "passive"))
      (node (ref "SW_DN") (pin "1") (pinfunction "1_1") (pintype "passive"))
      (node (ref "SW_ENT") (pin "1") (pinfunction "1_1") (pintype "passive"))
      (node (ref "SW_UP") (pin "1") (pinfunction "1_1") (pintype "passive"))
      (node (ref "TP_BAT_GND") (pin "TP") (pinfunction "TP_TP") (pintype "input"))
      (node (ref "TP_GND") (pin "TP") (pinfunction "TP_TP") (pintype "input"))
      (node (ref "U1") (pin "P$74") (pinfunction "VSS_PAD_P$74") (pintype "bidirectional"))
      (node (ref "U1") (pin "P$75") (pinfunction "VSS_PAD_P$75") (pintype "bidirectional"))
      (node (ref "U1") (pin "P$76") (pinfunction "VSS_PAD_P$76") (pintype "bidirectional"))
      (node (ref "U1") (pin "P$77") (pinfunction "VSS_PAD_P$77") (pintype "bidirectional"))
      (node (ref "U1") (pin "P$78") (pinfunction "VSS_PAD_P$78") (pintype "bidirectional"))
      (node (ref "U1") (pin "P$79") (pinfunction "VSS_PAD_P$79") (pintype "bidirectional"))
      (node (ref "U1") (pin "P$80") (pinfunction "VSS_PAD_P$80") (pintype "bidirectional"))
      (node (ref "U1") (pin "P$81") (pinfunction "VSS_PAD_P$81") (pintype "bidirectional"))
      (node (ref "U1") (pin "P$82") (pinfunction "VSS_PAD_P$82") (pintype "bidirectional"))
      (node (ref "U1") (pin "P$83") (pinfunction "VSS_PAD_P$83") (pintype "bidirectional"))
      (node (ref "U1") (pin "P$84") (pinfunction "VSS_PAD_P$84") (pintype "bidirectional"))
      (node (ref "U1") (pin "P$85") (pinfunction "VSS_PAD_P$85") (pintype "bidirectional"))
      (node (ref "U1") (pin "P$86") (pinfunction "VSS_PAD_P$86") (pintype "bidirectional"))
      (node (ref "U1") (pin "P$87") (pinfunction "VSS_PAD_P$87") (pintype "bidirectional"))
      (node (ref "U1") (pin "P$88") (pinfunction "VSS_PAD_P$88") (pintype "bidirectional"))
      (node (ref "U1") (pin "P$89") (pinfunction "VSS_PAD_P$89") (pintype "bidirectional"))
      (node (ref "U1") (pin "P$90") (pinfunction "VSS_PAD_P$90") (pintype "bidirectional"))
      (node (ref "U1") (pin "P$B7") (pinfunction "VSS_P$B7") (pintype "power_in"))
      (node (ref "U1") (pin "P$F23") (pinfunction "VSS_PA_P$F23") (pintype "bidirectional"))
      (node (ref "U3") (pin "1") (pinfunction "CTG_1") (pintype "power_in"))
      (node (ref "U3") (pin "4") (pinfunction "GND_4") (pintype "power_in"))
      (node (ref "U3") (pin "6") (pinfunction "QSTRT_6") (pintype "input"))
      (node (ref "U3") (pin "9") (pinfunction "EP_9") (pintype "power_in"))
      (node (ref "X1") (pin "2") (pinfunction "2_2") (pintype "passive"))
      (node (ref "X1") (pin "4") (pinfunction "4_4") (pintype "passive"))
    )
    (net (code "17") (name "HAPTIC_EN") (class "Default")
      (node (ref "IC2") (pin "A1") (pinfunction "EN_A1") (pintype "bidirectional"))
      (node (ref "U1") (pin "P$U1") (pinfunction "P0.12_P$U1") (pintype "bidirectional"))
    )
    (net (code "18") (name "IMU_INT1") (class "Default")
      (node (ref "IC3") (pin "5") (pinfunction "INT1_5") (pintype "bidirectional"))
      (node (ref "U1") (pin "P$N1") (pinfunction "P0.08_P$N1") (pintype "bidirectional"))
    )
    (net (code "19") (name "IMU_INT2") (class "Default")
      (node (ref "IC3") (pin "6") (pinfunction "INT2_6") (pintype "bidirectional"))
      (node (ref "U1") (pin "P$P2") (pinfunction "P1.08_P$P2") (pintype "bidirectional"))
    )
    (net (code "20") (name "LX1") (class "Default")
      (node (ref "IC9") (pin "B2") (pinfunction "SW1_1_B2") (pintype "bidirectional"))
      (node (ref "IC9") (pin "B3") (pinfunction "SW1_2_B3") (pintype "bidirectional"))
      (node (ref "L7") (pin "1") (pinfunction "1_1") (pintype "bidirectional"))
    )
    (net (code "21") (name "LX2") (class "Default")
      (node (ref "IC9") (pin "D2") (pinfunction "SW2_1_D2") (pintype "bidirectional"))
      (node (ref "IC9") (pin "D3") (pinfunction "SW2_2_D3") (pintype "bidirectional"))
      (node (ref "L7") (pin "2") (pinfunction "2_2") (pintype "bidirectional"))
    )
    (net (code "22") (name "MOSI") (class "Default")
      (node (ref "J1") (pin "14") (pinfunction "14_14") (pintype "bidirectional"))
      (node (ref "U1") (pin "P$B13") (pinfunction "P0.03/AIN1_P$B13") (pintype "bidirectional"))
    )
    (net (code "23") (name "Net-(ANT1-FEED)") (class "Default")
      (node (ref "ANT1") (pin "1") (pinfunction "FEED_1") (pintype "input"))
      (node (ref "C22") (pin "1") (pinfunction "1_1") (pintype "passive"))
      (node (ref "C4") (pin "1") (pinfunction "1_1") (pintype "passive"))
      (node (ref "L1") (pin "2") (pinfunction "2_2") (pintype "passive"))
    )
    (net (code "24") (name "Net-(D2-K)") (class "Default")
      (node (ref "C2-EP-DR") (pin "1") (pinfunction "1_1") (pintype "passive"))
      (node (ref "D2") (pin "1") (pinfunction "K_1") (pintype "bidirectional"))
      (node (ref "D4") (pin "2") (pinfunction "A_2") (pintype "bidirectional"))
    )
    (net (code "25") (name "Net-(D5-A)") (class "Default")
      (node (ref "C2-EP-DR") (pin "2") (pinfunction "2_2") (pintype "passive"))
      (node (ref "D5") (pin "2") (pinfunction "A_2") (pintype "bidirectional"))
      (node (ref "L5") (pin "2") (pinfunction "2_2") (pintype "bidirectional"))
      (node (ref "Q3") (pin "3") (pinfunction "D_3") (pintype "bidirectional"))
    )
    (net (code "26") (name "Net-(EPD_C1-Pad2)") (class "Default")
      (node (ref "EPD_C1") (pin "2") (pinfunction "2_2") (pintype "passive"))
      (node (ref "J1") (pin "5") (pinfunction "5_5") (pintype "bidirectional"))
    )
    (net (code "27") (name "Net-(EPD_C2-Pad2)") (class "Default")
      (node (ref "EPD_C2") (pin "2") (pinfunction "2_2") (pintype "passive"))
      (node (ref "J1") (pin "4") (pinfunction "4_4") (pintype "bidirectional"))
    )
    (net (code "28") (name "Net-(EPD_C6-Pad2)") (class "Default")
      (node (ref "EPD_C6") (pin "2") (pinfunction "2_2") (pintype "passive"))
      (node (ref "J1") (pin "18") (pinfunction "18_18") (pintype "bidirectional"))
    )
    (net (code "29") (name "Net-(EPD_C7-Pad2)") (class "Default")
      (node (ref "EPD_C7") (pin "2") (pinfunction "2_2") (pintype "passive"))
      (node (ref "J1") (pin "19") (pinfunction "19_19") (pintype "bidirectional"))
    )
    (net (code "30") (name "Net-(EPD_C8-Pad2)") (class "Default")
      (node (ref "EPD_C8") (pin "2") (pinfunction "2_2") (pintype "passive"))
      (node (ref "J1") (pin "20") (pinfunction "20_20") (pintype "bidirectional"))
    )
    (net (code "31") (name "Net-(EPD_C10-Pad2)") (class "Default")
      (node (ref "EPD_C10") (pin "2") (pinfunction "2_2") (pintype "passive"))
      (node (ref "J1") (pin "22") (pinfunction "22_22") (pintype "bidirectional"))
    )
    (net (code "32") (name "Net-(EPD_C12-Pad2)") (class "Default")
      (node (ref "EPD_C12") (pin "2") (pinfunction "2_2") (pintype "passive"))
      (node (ref "J1") (pin "24") (pinfunction "24_24") (pintype "bidirectional"))
    )
    (net (code "33") (name "Net-(IC1-TS{slash}MR)") (class "Default")
      (node (ref "IC1") (pin "D1") (pinfunction "TS/MR_D1") (pintype "bidirectional"))
      (node (ref "R9") (pin "2") (pinfunction "2_2") (pintype "bidirectional"))
    )
    (net (code "34") (name "Net-(IC2-REG)") (class "Default")
      (node (ref "C32") (pin "2") (pinfunction "2_2") (pintype "passive"))
      (node (ref "IC2") (pin "A2") (pinfunction "REG_A2") (pintype "bidirectional"))
    )
    (net (code "35") (name "Net-(IC3-SDO)") (class "Default")
      (node (ref "IC3") (pin "1") (pinfunction "SDO_1") (pintype "bidirectional"))
      (node (ref "R3") (pin "2") (pinfunction "2_2") (pintype "bidirectional"))
    )
    (net (code "36") (name "Net-(IC9-SCL)") (class "Default")
      (node (ref "IC9") (pin "D1") (pinfunction "SCL_D1") (pintype "bidirectional"))
      (node (ref "R4") (pin "1") (pinfunction "1_1") (pintype "bidirectional"))
    )
    (net (code "37") (name "Net-(IC9-SDA)") (class "Default")
      (node (ref "IC9") (pin "E1") (pinfunction "SDA_E1") (pintype "bidirectional"))
      (node (ref "R2") (pin "1") (pinfunction "1_1") (pintype "bidirectional"))
    )
    (net (code "38") (name "Net-(J4-CC1)") (class "Default")
      (node (ref "J4") (pin "A5") (pinfunction "CC1_A5") (pintype "bidirectional"))
      (node (ref "R1_USB") (pin "2") (pinfunction "2_2") (pintype "bidirectional"))
    )
    (net (code "39") (name "Net-(J4-CC2)") (class "Default")
      (node (ref "J4") (pin "B5") (pinfunction "CC2_B5") (pintype "bidirectional"))
      (node (ref "R2_USB") (pin "1") (pinfunction "1_1") (pintype "bidirectional"))
    )
    (net (code "40") (name "Net-(L2-Pad2)") (class "Default")
      (node (ref "L2") (pin "2") (pinfunction "2_2") (pintype "passive"))
      (node (ref "L3") (pin "1") (pinfunction "1_1") (pintype "passive"))
    )
    (net (code "41") (name "Net-(R1_EP_DP-Pad1)") (class "Default")
      (node (ref "R1_EP_DP") (pin "1") (pinfunction "1_1") (pintype "bidirectional"))
      (node (ref "R_TYPE_SEL") (pin "2") (pinfunction "2_2") (pintype "bidirectional"))
      (node (ref "SJ1") (pin "2") (pinfunction "2_2") (pintype "passive"))
    )
    (net (code "42") (name "Net-(U1-ANT)") (class "Default")
      (node (ref "C3") (pin "1") (pinfunction "1_1") (pintype "passive"))
      (node (ref "L1") (pin "1") (pinfunction "1_1") (pintype "passive"))
      (node (ref "U1") (pin "P$H23") (pinfunction "ANT_P$H23") (pintype "bidirectional"))
    )
    (net (code "43") (name "Net-(U1-DCC)") (class "Default")
      (node (ref "L2") (pin "1") (pinfunction "1_1") (pintype "passive"))
      (node (ref "U1") (pin "P$B3") (pinfunction "DCC_P$B3") (pintype "output"))
    )
    (net (code "44") (name "Net-(U1-DEC2)") (class "Default")
      (node (ref "C13") (pin "1") (pinfunction "1_1") (pintype "passive"))
      (node (ref "U1") (pin "P$A18") (pinfunction "DEC2_P$A18") (pintype "bidirectional"))
    )
    (net (code "45") (name "Net-(U1-DEC3V3)") (class "Default")
      (node (ref "C20") (pin "1") (pinfunction "1_1") (pintype "passive"))
      (node (ref "U1") (pin "P$AC5") (pinfunction "DEC3V3_P$AC5") (pintype "bidirectional"))
    )
    (net (code "46") (name "Net-(U1-DEC5)") (class "Default")
      (node (ref "C9") (pin "1") (pinfunction "1_1") (pintype "passive"))
      (node (ref "U1") (pin "P$N24") (pinfunction "DEC5_P$N24") (pintype "bidirectional"))
    )
    (net (code "47") (name "Net-(U1-P0.00{slash}XL1)") (class "Default")
      (node (ref "C17") (pin "2") (pinfunction "2_2") (pintype "passive"))
      (node (ref "U1") (pin "P$D2") (pinfunction "P0.00/XL1_P$D2") (pintype "bidirectional"))
      (node (ref "X2") (pin "1") (pinfunction "1_1") (pintype "passive"))
    )
    (net (code "48") (name "Net-(U1-P0.01{slash}XL2)") (class "Default")
      (node (ref "C18") (pin "2") (pinfunction "2_2") (pintype "passive"))
      (node (ref "U1") (pin "P$F2") (pinfunction "P0.01/XL2_P$F2") (pintype "bidirectional"))
      (node (ref "X2") (pin "2") (pinfunction "2_2") (pintype "passive"))
    )
    (net (code "49") (name "Net-(U1-XC1)") (class "Default")
      (node (ref "C1") (pin "1") (pinfunction "1_1") (pintype "passive"))
      (node (ref "U1") (pin "P$B24") (pinfunction "XC1_P$B24") (pintype "input"))
      (node (ref "X1") (pin "1") (pinfunction "1_1") (pintype "passive"))
    )
    (net (code "50") (name "Net-(U1-XC2)") (class "Default")
      (node (ref "C2") (pin "1") (pinfunction "1_1") (pintype "passive"))
      (node (ref "U1") (pin "P$A23") (pinfunction "XC2_P$A23") (pintype "output"))
      (node (ref "X1") (pin "3") (pinfunction "3_3") (pintype "passive"))
    )
    (net (code "51") (name "OUT+") (class "Default")
      (node (ref "IC2") (pin "A3") (pinfunction "OUT+_A3") (pintype "bidirectional"))
      (node (ref "TP_OP") (pin "TP") (pinfunction "TP_TP") (pintype "input"))
    )
    (net (code "52") (name "OUT-") (class "Default")
      (node (ref "IC2") (pin "C3") (pinfunction "OUT-_C3") (pintype "bidirectional"))
      (node (ref "TP_ON") (pin "TP") (pinfunction "TP_TP") (pintype "input"))
    )
    (net (code "53") (name "P0.04") (class "Default")
      (node (ref "U1") (pin "P$J1") (pinfunction "P0.04/AIN2_P$J1") (pintype "bidirectional"))
    )
    (net (code "54") (name "P0.09") (class "Default")
      (node (ref "U1") (pin "P$L24") (pinfunction "P0.09/NFC1_P$L24") (pintype "bidirectional"))
    )
    (net (code "55") (name "P0.13") (class "Default")
      (node (ref "C30") (pin "2") (pinfunction "2_2") (pintype "passive"))
      (node (ref "R5") (pin "1") (pinfunction "1_1") (pintype "bidirectional"))
      (node (ref "SW_UP") (pin "2") (pinfunction "2_2") (pintype "passive"))
      (node (ref "U1") (pin "P$AD8") (pinfunction "P0.13_P$AD8") (pintype "bidirectional"))
    )
    (net (code "56") (name "P0.14") (class "Default")
      (node (ref "C31") (pin "2") (pinfunction "2_2") (pintype "passive"))
      (node (ref "R8") (pin "1") (pinfunction "1_1") (pintype "bidirectional"))
      (node (ref "SW_ENT") (pin "2") (pinfunction "2_2") (pintype "passive"))
      (node (ref "U1") (pin "P$AC9") (pinfunction "P0.14_P$AC9") (pintype "bidirectional"))
    )
    (net (code "57") (name "P0.19") (class "Default")
      (node (ref "U1") (pin "P$AC15") (pinfunction "P0.19_P$AC15") (pintype "bidirectional"))
    )
    (net (code "58") (name "P0.20") (class "Default")
      (node (ref "U1") (pin "P$AD16") (pinfunction "P0.20_P$AD16") (pintype "bidirectional"))
    )
    (net (code "59") (name "P0.21") (class "Default")
      (node (ref "U1") (pin "P$AC17") (pinfunction "P0.21_P$AC17") (pintype "bidirectional"))
    )
    (net (code "60") (name "P0.22") (class "Default")
      (node (ref "U1") (pin "P$AD18") (pinfunction "P0.22_P$AD18") (pintype "bidirectional"))
    )
    (net (code "61") (name "P0.23") (class "Default")
      (node (ref "U1") (pin "P$AC19") (pinfunction "P0.23_P$AC19") (pintype "bidirectional"))
    )
    (net (code "62") (name "P0.24") (class "Default")
      (node (ref "U1") (pin "P$AD20") (pinfunction "P0.24_P$AD20") (pintype "bidirectional"))
    )
    (net (code "63") (name "P0.25") (class "Default")
      (node (ref "U1") (pin "P$AC21") (pinfunction "P0.25_P$AC21") (pintype "bidirectional"))
    )
    (net (code "64") (name "P0.26") (class "Default")
      (node (ref "U1") (pin "P$G1") (pinfunction "P0.26_P$G1") (pintype "bidirectional"))
    )
    (net (code "65") (name "P0.27") (class "Default")
      (node (ref "U1") (pin "P$H2") (pinfunction "P0.27_P$H2") (pintype "bidirectional"))
    )
    (net (code "66") (name "P0.28") (class "Default")
      (node (ref "U1") (pin "P$B11") (pinfunction "P0.28/AIN4_P$B11") (pintype "bidirectional"))
    )
    (net (code "67") (name "P0.29") (class "Default")
      (node (ref "U1") (pin "P$A10") (pinfunction "P0.29/AIN5_P$A10") (pintype "bidirectional"))
    )
    (net (code "68") (name "P0.30") (class "Default")
      (node (ref "U1") (pin "P$B9") (pinfunction "P0.30/AIN6_P$B9") (pintype "bidirectional"))
    )
    (net (code "69") (name "P0.31") (class "Default")
      (node (ref "U1") (pin "P$A8") (pinfunction "P0.31/AIN7_P$A8") (pintype "bidirectional"))
    )
    (net (code "70") (name "P1.01") (class "Default")
      (node (ref "Q1") (pin "1") (pinfunction "G_1") (pintype "bidirectional"))
      (node (ref "R_PWR_EPD") (pin "1") (pinfunction "1_1") (pintype "bidirectional"))
      (node (ref "U1") (pin "P$Y23") (pinfunction "P1.01_P$Y23") (pintype "bidirectional"))
    )
    (net (code "71") (name "P1.02") (class "Default")
      (node (ref "C29") (pin "2") (pinfunction "2_2") (pintype "passive"))
      (node (ref "R7") (pin "1") (pinfunction "1_1") (pintype "bidirectional"))
      (node (ref "SW_DN") (pin "2") (pinfunction "2_2") (pintype "passive"))
      (node (ref "U1") (pin "P$W24") (pinfunction "P1.02_P$W24") (pintype "bidirectional"))
    )
    (net (code "72") (name "P1.03") (class "Default")
      (node (ref "U1") (pin "P$V23") (pinfunction "P1.03_P$V23") (pintype "bidirectional"))
    )
    (net (code "73") (name "P1.04") (class "Default")
      (node (ref "U1") (pin "P$U24") (pinfunction "P1.04_P$U24") (pintype "bidirectional"))
    )
    (net (code "74") (name "P1.05") (class "Default")
      (node (ref "U1") (pin "P$T23") (pinfunction "P1.05_P$T23") (pintype "bidirectional"))
    )
    (net (code "75") (name "P1.06") (class "Default")
      (node (ref "U1") (pin "P$R24") (pinfunction "P1.06_P$R24") (pintype "bidirectional"))
    )
    (net (code "76") (name "P1.07") (class "Default")
      (node (ref "U1") (pin "P$P23") (pinfunction "P1.07_P$P23") (pintype "bidirectional"))
    )
    (net (code "77") (name "P1.09") (class "Default")
      (node (ref "U1") (pin "P$R1") (pinfunction "P1.09_P$R1") (pintype "bidirectional"))
    )
    (net (code "78") (name "P1.10") (class "Default")
      (node (ref "U1") (pin "P$A20") (pinfunction "P1.10_P$A20") (pintype "bidirectional"))
    )
    (net (code "79") (name "P1.11") (class "Default")
      (node (ref "U1") (pin "P$B19") (pinfunction "P1.11_P$B19") (pintype "bidirectional"))
    )
    (net (code "80") (name "P1.12") (class "Default")
      (node (ref "U1") (pin "P$B17") (pinfunction "P1.12_P$B17") (pintype "bidirectional"))
    )
    (net (code "81") (name "P1.13") (class "Default")
      (node (ref "U1") (pin "P$A16") (pinfunction "P1.13_P$A16") (pintype "bidirectional"))
    )
    (net (code "82") (name "P1.14") (class "Default")
      (node (ref "U1") (pin "P$B15") (pinfunction "P1.14_P$B15") (pintype "bidirectional"))
    )
    (net (code "83") (name "P1.15") (class "Default")
      (node (ref "U1") (pin "P$A14") (pinfunction "P1.15_P$A14") (pintype "bidirectional"))
    )
    (net (code "84") (name "PMIC_INT") (class "Default")
      (node (ref "IC1") (pin "A1") (pinfunction "~{INT}_A1") (pintype "bidirectional"))
      (node (ref "U1") (pin "P$T2") (pinfunction "P0.11_P$T2") (pintype "bidirectional"))
    )
    (net (code "85") (name "PREVGH") (class "Default")
      (node (ref "D5") (pin "1") (pinfunction "K_1") (pintype "bidirectional"))
      (node (ref "EPD_C9") (pin "2") (pinfunction "2_2") (pintype "passive"))
      (node (ref "J1") (pin "21") (pinfunction "21_21") (pintype "bidirectional"))
    )
    (net (code "86") (name "PREVGL") (class "Default")
      (node (ref "D2") (pin "2") (pinfunction "A_2") (pintype "bidirectional"))
      (node (ref "EPD_C11") (pin "2") (pinfunction "2_2") (pintype "passive"))
      (node (ref "J1") (pin "23") (pinfunction "23_23") (pintype "bidirectional"))
    )
    (net (code "87") (name "RESE") (class "Default")
      (node (ref "J1") (pin "3") (pinfunction "3_3") (pintype "bidirectional"))
      (node (ref "Q3") (pin "2") (pinfunction "S_2") (pintype "bidirectional"))
      (node (ref "R1_EP_DP") (pin "2") (pinfunction "2_2") (pintype "bidirectional"))
    )
    (net (code "88") (name "RESET") (class "Default")
      (node (ref "J2") (pin "6") (pinfunction "6_6") (pintype "bidirectional"))
      (node (ref "TP_RESET") (pin "TP") (pinfunction "TP_TP") (pintype "input"))
      (node (ref "U1") (pin "P$AC13") (pinfunction "P0.18/RESET_P$AC13") (pintype "bidirectional"))
    )
    (net (code "89") (name "SCK") (class "Default")
      (node (ref "J1") (pin "13") (pinfunction "13_13") (pintype "bidirectional"))
      (node (ref "U1") (pin "P$A12") (pinfunction "P0.02/AIN0_P$A12") (pintype "bidirectional"))
    )
    (net (code "90") (name "SCL") (class "Default")
      (node (ref "IC2") (pin "C1") (pinfunction "SCL_C1") (pintype "bidirectional"))
      (node (ref "IC3") (pin "12") (pinfunction "SCX_12") (pintype "bidirectional"))
      (node (ref "R17") (pin "2") (pinfunction "2_2") (pintype "bidirectional"))
      (node (ref "R4") (pin "2") (pinfunction "2_2") (pintype "bidirectional"))
      (node (ref "TP_SCL") (pin "TP") (pinfunction "TP_TP") (pintype "input"))
      (node (ref "U3") (pin "7") (pinfunction "SCL_7") (pintype "input"))
    )
    (net (code "91") (name "SCL{slash}2.4C") (class "Default")
      (node (ref "IC1") (pin "B1") (pinfunction "SCL_B1") (pintype "bidirectional"))
    )
    (net (code "92") (name "SDA") (class "Default")
      (node (ref "IC1") (pin "C1") (pinfunction "SDA_C1") (pintype "bidirectional"))
      (node (ref "IC2") (pin "B2") (pinfunction "SDA_B2") (pintype "bidirectional"))
      (node (ref "IC3") (pin "2") (pinfunction "SDX_2") (pintype "bidirectional"))
      (node (ref "R18") (pin "2") (pinfunction "2_2") (pintype "bidirectional"))
      (node (ref "R2") (pin "2") (pinfunction "2_2") (pintype "bidirectional"))
      (node (ref "TP_SDA") (pin "TP") (pinfunction "TP_TP") (pintype "input"))
      (node (ref "U1") (pin "P$L1") (pinfunction "P0.06_P$L1") (pintype "bidirectional"))
      (node (ref "U3") (pin "8") (pinfunction "SDA_8") (pintype "bidirectional"))
    )
    (net (code "93") (name "SLC") (class "Default")
      (node (ref "U1") (pin "P$M2") (pinfunction "P0.07_P$M2") (pintype "bidirectional"))
    )
    (net (code "94") (name "SWDCLK") (class "Default")
      (node (ref "J2") (pin "4") (pinfunction "4_4") (pintype "bidirectional"))
      (node (ref "TP_SWDCLK") (pin "TP") (pinfunction "TP_TP") (pintype "input"))
      (node (ref "U1") (pin "P$AA24") (pinfunction "SWDCLK_P$AA24") (pintype "input"))
    )
    (net (code "95") (name "SWDIO") (class "Default")
      (node (ref "J2") (pin "2") (pinfunction "2_2") (pintype "bidirectional"))
      (node (ref "TP_SWDIO") (pin "TP") (pinfunction "TP_TP") (pintype "input"))
      (node (ref "U1") (pin "P$AC24") (pinfunction "SWDIO_P$AC24") (pintype "bidirectional"))
    )
    (net (code "96") (name "SWO") (class "Default")
      (node (ref "TP_SWO") (pin "TP") (pinfunction "TP_TP") (pintype "input"))
      (node (ref "U1") (pin "P$AD22") (pinfunction "P1.00_P$AD22") (pintype "bidirectional"))
    )
    (net (code "97") (name "VBAT") (class "Default")
      (node (ref "C27") (pin "2") (pinfunction "2_2") (pintype "passive"))
      (node (ref "C37") (pin "2") (pinfunction "2_2") (pintype "passive"))
      (node (ref "IC1") (pin "C2") (pinfunction "BAT_C2") (pintype "bidirectional"))
      (node (ref "TP_VBAT") (pin "TP") (pinfunction "TP_TP") (pintype "input"))
      (node (ref "U3") (pin "2") (pinfunction "CELL_2") (pintype "power_in"))
      (node (ref "U3") (pin "3") (pinfunction "VDD_3") (pintype "power_in"))
    )
    (net (code "98") (name "VBUS") (class "Default")
      (node (ref "C21") (pin "1") (pinfunction "1_1") (pintype "passive"))
      (node (ref "C42") (pin "1") (pinfunction "1_1") (pintype "passive"))
      (node (ref "C43") (pin "1") (pinfunction "1_1") (pintype "passive"))
      (node (ref "D3") (pin "5") (pinfunction "VBUS_5") (pintype "bidirectional"))
      (node (ref "J4") (pin "A4_B9") (pinfunction "VBUS_A4_B9") (pintype "power_in"))
      (node (ref "J4") (pin "A9_B4") (pinfunction "VBUS_A9_B4") (pintype "power_in"))
      (node (ref "U1") (pin "P$AD2") (pinfunction "VBUS_P$AD2") (pintype "power_in"))
    )
    (net (code "99") (name "VBUS{slash}2.6D") (class "Default")
      (node (ref "C38") (pin "2") (pinfunction "2_2") (pintype "passive"))
      (node (ref "IC1") (pin "A2") (pinfunction "IN_A2") (pintype "bidirectional"))
    )
    (net (code "100") (name "VREG") (class "Default")
      (node (ref "C23") (pin "2") (pinfunction "2_2") (pintype "passive"))
      (node (ref "C24") (pin "2") (pinfunction "2_2") (pintype "passive"))
      (node (ref "C39") (pin "1") (pinfunction "1_1") (pintype "passive"))
      (node (ref "IC1") (pin "B2") (pinfunction "SYS_B2") (pintype "bidirectional"))
      (node (ref "IC9") (pin "A1") (pinfunction "EN_A1") (pintype "bidirectional"))
      (node (ref "IC9") (pin "A2") (pinfunction "VIN_1_A2") (pintype "bidirectional"))
      (node (ref "IC9") (pin "A3") (pinfunction "VIN_2_A3") (pintype "bidirectional"))
      (node (ref "TP_VREG") (pin "TP") (pinfunction "TP_TP") (pintype "input"))
    )
    (net (code "101") (name "unconnected-(ANT1-NC-Pad2)") (class "Default")
      (node (ref "ANT1") (pin "2") (pinfunction "NC_2") (pintype "no_connect"))
    )
    (net (code "102") (name "unconnected-(IC3-ASCL-Pad11)") (class "Default")
      (node (ref "IC3") (pin "11") (pinfunction "ASCL_11") (pintype "bidirectional"))
    )
    (net (code "103") (name "unconnected-(IC3-ASDA-Pad4)") (class "Default")
      (node (ref "IC3") (pin "4") (pinfunction "ASDA_4") (pintype "bidirectional"))
    )
    (net (code "104") (name "unconnected-(J1-Pad1)") (class "Default")
      (node (ref "J1") (pin "1") (pinfunction "1_1") (pintype "bidirectional"))
    )
    (net (code "105") (name "unconnected-(J1-Pad6)") (class "Default")
      (node (ref "J1") (pin "6") (pinfunction "6_6") (pintype "bidirectional"))
    )
    (net (code "106") (name "unconnected-(J1-Pad7)") (class "Default")
      (node (ref "J1") (pin "7") (pinfunction "7_7") (pintype "bidirectional"))
    )
    (net (code "107") (name "unconnected-(J4-SBU1-PadA8)") (class "Default")
      (node (ref "J4") (pin "A8") (pinfunction "SBU1_A8") (pintype "bidirectional"))
    )
    (net (code "108") (name "unconnected-(J4-SBU2-PadB8)") (class "Default")
      (node (ref "J4") (pin "B8") (pinfunction "SBU2_B8") (pintype "bidirectional"))
    )
    (net (code "109") (name "unconnected-(U1-DCCH-PadP$AB2)") (class "Default")
      (node (ref "U1") (pin "P$AB2") (pinfunction "DCCH_P$AB2") (pintype "bidirectional"))
    )
  )
)
